# PAD1v2.net
KiCad netlist of a schematic drawn in EAGLE
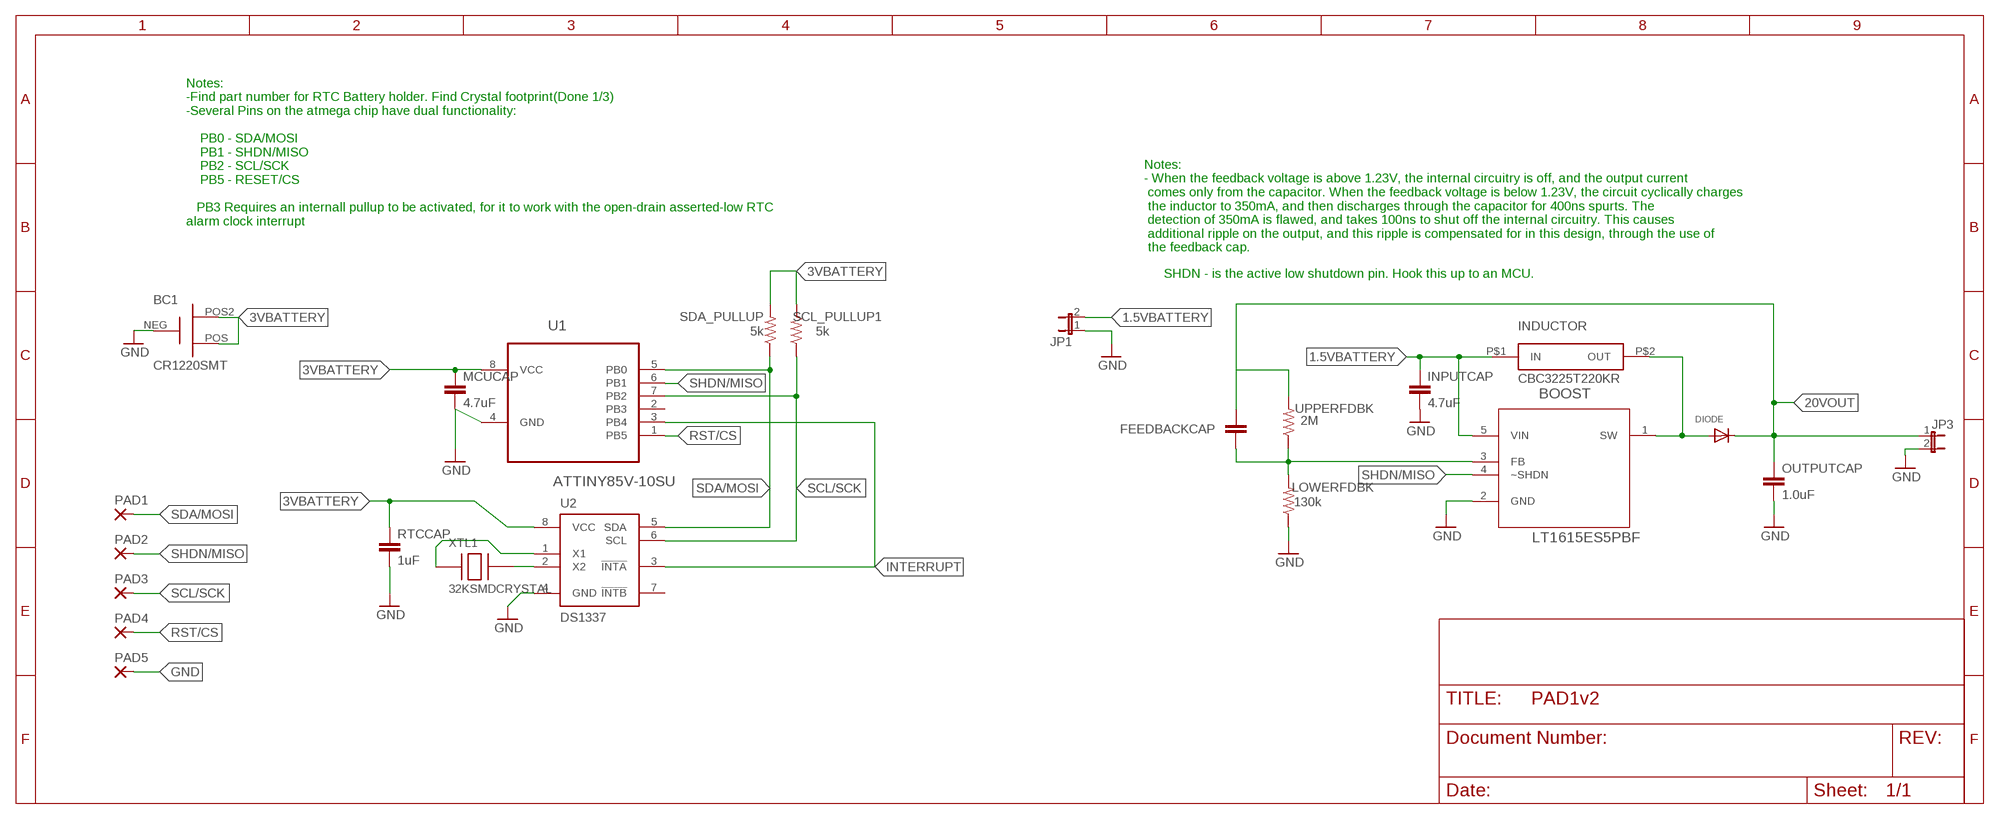
[diagram p0: schematic, sheet 1]

(export (version "E")
  (design (tool "Eeschema 10.0.6"))
  (components
    (comp (ref "BC1")
      (value "CR1220SMT")
      (footprint "eagle-import:3000TR")
      (libsource (lib "eagle-import") (part "CR1220SMT"))
    )
    (comp (ref "BOOST")
      (value "LT1615ES5PBF")
      (footprint "eagle-import:SOT95P280X145-5N")
      (fields (field (name "MPN") "LT1615ES5#PBF"))
      (libsource (lib "eagle-import") (part "LT1615ES5PBF"))
    )
    (comp (ref "DIODE")
      (value "DIODESOD-123")
      (footprint "eagle-import:SOD-123")
      (libsource (lib "eagle-import") (part "DIODESOD-123"))
    )
    (comp (ref "FEEDBACKCAP")
      (value "4.7pF")
      (footprint "eagle-import:1206")
      (libsource (lib "eagle-import") (part "CAP1206"))
    )
    (comp (ref "INDUCTOR")
      (value "CBC3225T220KR")
      (footprint "eagle-import:1210")
      (libsource (lib "eagle-import") (part "CBC3225T220KR"))
    )
    (comp (ref "INPUTCAP")
      (value "4.7uF")
      (footprint "eagle-import:1206")
      (libsource (lib "eagle-import") (part "CAP1206"))
    )
    (comp (ref "JP1")
      (value "JUMPER-2PTH")
      (footprint "eagle-import:1X02")
      (libsource (lib "eagle-import") (part "JUMPER-2PTH"))
    )
    (comp (ref "JP3")
      (value "JUMPER-2PTH_LOCK")
      (footprint "eagle-import:1X02_LOCK")
      (libsource (lib "eagle-import") (part "JUMPER-2PTH_LOCK"))
    )
    (comp (ref "LOWERFDBK")
      (value "130k")
      (footprint "eagle-import:1206")
      (libsource (lib "eagle-import") (part "RESISTOR1206"))
    )
    (comp (ref "MCUCAP")
      (value "4.7uF")
      (footprint "eagle-import:1206")
      (libsource (lib "eagle-import") (part "CAP1206"))
    )
    (comp (ref "OUTPUTCAP")
      (value "1.0uF")
      (footprint "eagle-import:1206")
      (libsource (lib "eagle-import") (part "CAP1206"))
    )
    (comp (ref "PAD1")
      (value "1,6/0,8")
      (footprint "eagle-import:1,6_0,8")
      (libsource (lib "eagle-import") (part "1,6/0,8"))
    )
    (comp (ref "PAD2")
      (value "1,6/0,8")
      (footprint "eagle-import:1,6_0,8")
      (libsource (lib "eagle-import") (part "1,6/0,8"))
    )
    (comp (ref "PAD3")
      (value "1,6/0,8")
      (footprint "eagle-import:1,6_0,8")
      (libsource (lib "eagle-import") (part "1,6/0,8"))
    )
    (comp (ref "PAD4")
      (value "1,6/0,8")
      (footprint "eagle-import:1,6_0,8")
      (libsource (lib "eagle-import") (part "1,6/0,8"))
    )
    (comp (ref "PAD5")
      (value "1,6/0,8")
      (footprint "eagle-import:1,6_0,8")
      (libsource (lib "eagle-import") (part "1,6/0,8"))
    )
    (comp (ref "RTCCAP")
      (value "1uF")
      (footprint "eagle-import:1206")
      (libsource (lib "eagle-import") (part "CAP1206"))
    )
    (comp (ref "SCL_PULLUP1")
      (value "5k")
      (footprint "eagle-import:1206")
      (libsource (lib "eagle-import") (part "RESISTOR1206"))
    )
    (comp (ref "SDA_PULLUP")
      (value "5k")
      (footprint "eagle-import:1206")
      (libsource (lib "eagle-import") (part "RESISTOR1206"))
    )
    (comp (ref "U1")
      (value "ATTINY85V-10SU")
      (footprint "eagle-import:SOIC127P798X216-8N")
      (libsource (lib "eagle-import") (part "ATTINY85V-10SU"))
    )
    (comp (ref "U2")
      (value "DS1337")
      (footprint "eagle-import:UMAX8")
      (libsource (lib "eagle-import") (part "DS1337"))
    )
    (comp (ref "UPPERFDBK")
      (value "2M")
      (footprint "eagle-import:1206")
      (libsource (lib "eagle-import") (part "RESISTOR1206"))
    )
    (comp (ref "XTL1")
      (value "32KSMDCRYSTAL")
      (footprint "eagle-import:4-SMD")
      (libsource (lib "eagle-import") (part "32KSMDCRYSTAL"))
    )
  )
  (nets
    (net (code "1") (name "1.5VBATTERY") (class "Default")
      (node (ref "BOOST") (pin "5") (pinfunction "VIN_5") (pintype "power_in"))
      (node (ref "INDUCTOR") (pin "P$1") (pinfunction "IN_P$1") (pintype "bidirectional"))
      (node (ref "INPUTCAP") (pin "1") (pinfunction "1_1") (pintype "passive"))
      (node (ref "JP1") (pin "2") (pinfunction "2_2") (pintype "passive"))
    )
    (net (code "2") (name "3VBATTERY") (class "Default")
      (node (ref "BC1") (pin "POS") (pinfunction "POS_POS") (pintype "bidirectional"))
      (node (ref "BC1") (pin "POS2") (pinfunction "POS2_POS2") (pintype "bidirectional"))
      (node (ref "MCUCAP") (pin "1") (pinfunction "1_1") (pintype "passive"))
      (node (ref "RTCCAP") (pin "1") (pinfunction "1_1") (pintype "passive"))
      (node (ref "SCL_PULLUP1") (pin "2") (pinfunction "2_2") (pintype "passive"))
      (node (ref "SDA_PULLUP") (pin "2") (pinfunction "2_2") (pintype "passive"))
      (node (ref "U1") (pin "8") (pinfunction "VCC_8") (pintype "power_in"))
      (node (ref "U2") (pin "8") (pinfunction "VCC_8") (pintype "bidirectional"))
    )
    (net (code "3") (name "20VOUT") (class "Default")
      (node (ref "DIODE") (pin "C") (pinfunction "C_C") (pintype "passive"))
      (node (ref "FEEDBACKCAP") (pin "1") (pinfunction "1_1") (pintype "passive"))
      (node (ref "JP3") (pin "1") (pinfunction "1_1") (pintype "passive"))
      (node (ref "OUTPUTCAP") (pin "1") (pinfunction "1_1") (pintype "passive"))
      (node (ref "UPPERFDBK") (pin "2") (pinfunction "2_2") (pintype "passive"))
    )
    (net (code "4") (name "GND") (class "Default")
      (node (ref "BC1") (pin "NEG") (pinfunction "NEG_NEG") (pintype "bidirectional"))
      (node (ref "BOOST") (pin "2") (pinfunction "GND_2") (pintype "passive"))
      (node (ref "INPUTCAP") (pin "2") (pinfunction "2_2") (pintype "passive"))
      (node (ref "JP1") (pin "1") (pinfunction "1_1") (pintype "passive"))
      (node (ref "JP3") (pin "2") (pinfunction "2_2") (pintype "passive"))
      (node (ref "LOWERFDBK") (pin "1") (pinfunction "1_1") (pintype "passive"))
      (node (ref "MCUCAP") (pin "2") (pinfunction "2_2") (pintype "passive"))
      (node (ref "OUTPUTCAP") (pin "2") (pinfunction "2_2") (pintype "passive"))
      (node (ref "PAD5") (pin "1") (pinfunction "P_1") (pintype "passive"))
      (node (ref "RTCCAP") (pin "2") (pinfunction "2_2") (pintype "passive"))
      (node (ref "U1") (pin "4") (pinfunction "GND_4") (pintype "passive"))
      (node (ref "U2") (pin "4") (pinfunction "GND_4") (pintype "bidirectional"))
    )
    (net (code "5") (name "INTERRUPT") (class "Default")
      (node (ref "U1") (pin "3") (pinfunction "PB4_3") (pintype "bidirectional"))
      (node (ref "U2") (pin "3") (pinfunction "~{INTA}_3") (pintype "bidirectional"))
    )
    (net (code "6") (name "Net-(BOOST-FB)") (class "Default")
      (node (ref "BOOST") (pin "3") (pinfunction "FB_3") (pintype "input"))
      (node (ref "FEEDBACKCAP") (pin "2") (pinfunction "2_2") (pintype "passive"))
      (node (ref "LOWERFDBK") (pin "2") (pinfunction "2_2") (pintype "passive"))
      (node (ref "UPPERFDBK") (pin "1") (pinfunction "1_1") (pintype "passive"))
    )
    (net (code "7") (name "Net-(BOOST-SW)") (class "Default")
      (node (ref "BOOST") (pin "1") (pinfunction "SW_1") (pintype "output"))
      (node (ref "DIODE") (pin "A") (pinfunction "A_A") (pintype "passive"))
      (node (ref "INDUCTOR") (pin "P$2") (pinfunction "OUT_P$2") (pintype "bidirectional"))
    )
    (net (code "8") (name "Net-(U2-X1)") (class "Default")
      (node (ref "U2") (pin "1") (pinfunction "X1_1") (pintype "bidirectional"))
      (node (ref "XTL1") (pin "XTAL1") (pinfunction "XTAL1_XTAL1") (pintype "bidirectional"))
    )
    (net (code "9") (name "Net-(U2-X2)") (class "Default")
      (node (ref "U2") (pin "2") (pinfunction "X2_2") (pintype "bidirectional"))
      (node (ref "XTL1") (pin "XTAL2") (pinfunction "XTAL2_XTAL2") (pintype "bidirectional"))
    )
    (net (code "10") (name "RST{slash}CS") (class "Default")
      (node (ref "PAD4") (pin "1") (pinfunction "P_1") (pintype "passive"))
      (node (ref "U1") (pin "1") (pinfunction "PB5_1") (pintype "bidirectional"))
    )
    (net (code "11") (name "SCL{slash}SCK") (class "Default")
      (node (ref "PAD3") (pin "1") (pinfunction "P_1") (pintype "passive"))
      (node (ref "SCL_PULLUP1") (pin "1") (pinfunction "1_1") (pintype "passive"))
      (node (ref "U1") (pin "7") (pinfunction "PB2_7") (pintype "bidirectional"))
      (node (ref "U2") (pin "6") (pinfunction "SCL_6") (pintype "bidirectional"))
    )
    (net (code "12") (name "SDA{slash}MOSI") (class "Default")
      (node (ref "PAD1") (pin "1") (pinfunction "P_1") (pintype "passive"))
      (node (ref "SDA_PULLUP") (pin "1") (pinfunction "1_1") (pintype "passive"))
      (node (ref "U1") (pin "5") (pinfunction "PB0_5") (pintype "bidirectional"))
      (node (ref "U2") (pin "5") (pinfunction "SDA_5") (pintype "bidirectional"))
    )
    (net (code "13") (name "SHDN{slash}MISO") (class "Default")
      (node (ref "BOOST") (pin "4") (pinfunction "~{SHDN}_4") (pintype "input"))
      (node (ref "PAD2") (pin "1") (pinfunction "P_1") (pintype "passive"))
      (node (ref "U1") (pin "6") (pinfunction "PB1_6") (pintype "bidirectional"))
    )
    (net (code "14") (name "unconnected-(U1-PB3-Pad2)") (class "Default")
      (node (ref "U1") (pin "2") (pinfunction "PB3_2") (pintype "bidirectional"))
    )
    (net (code "15") (name "unconnected-(U2-~{INTB}-Pad7)") (class "Default")
      (node (ref "U2") (pin "7") (pinfunction "~{INTB}_7") (pintype "bidirectional"))
    )
  )
)
